# Motors.net
KiCad netlist of a schematic drawn in EAGLE
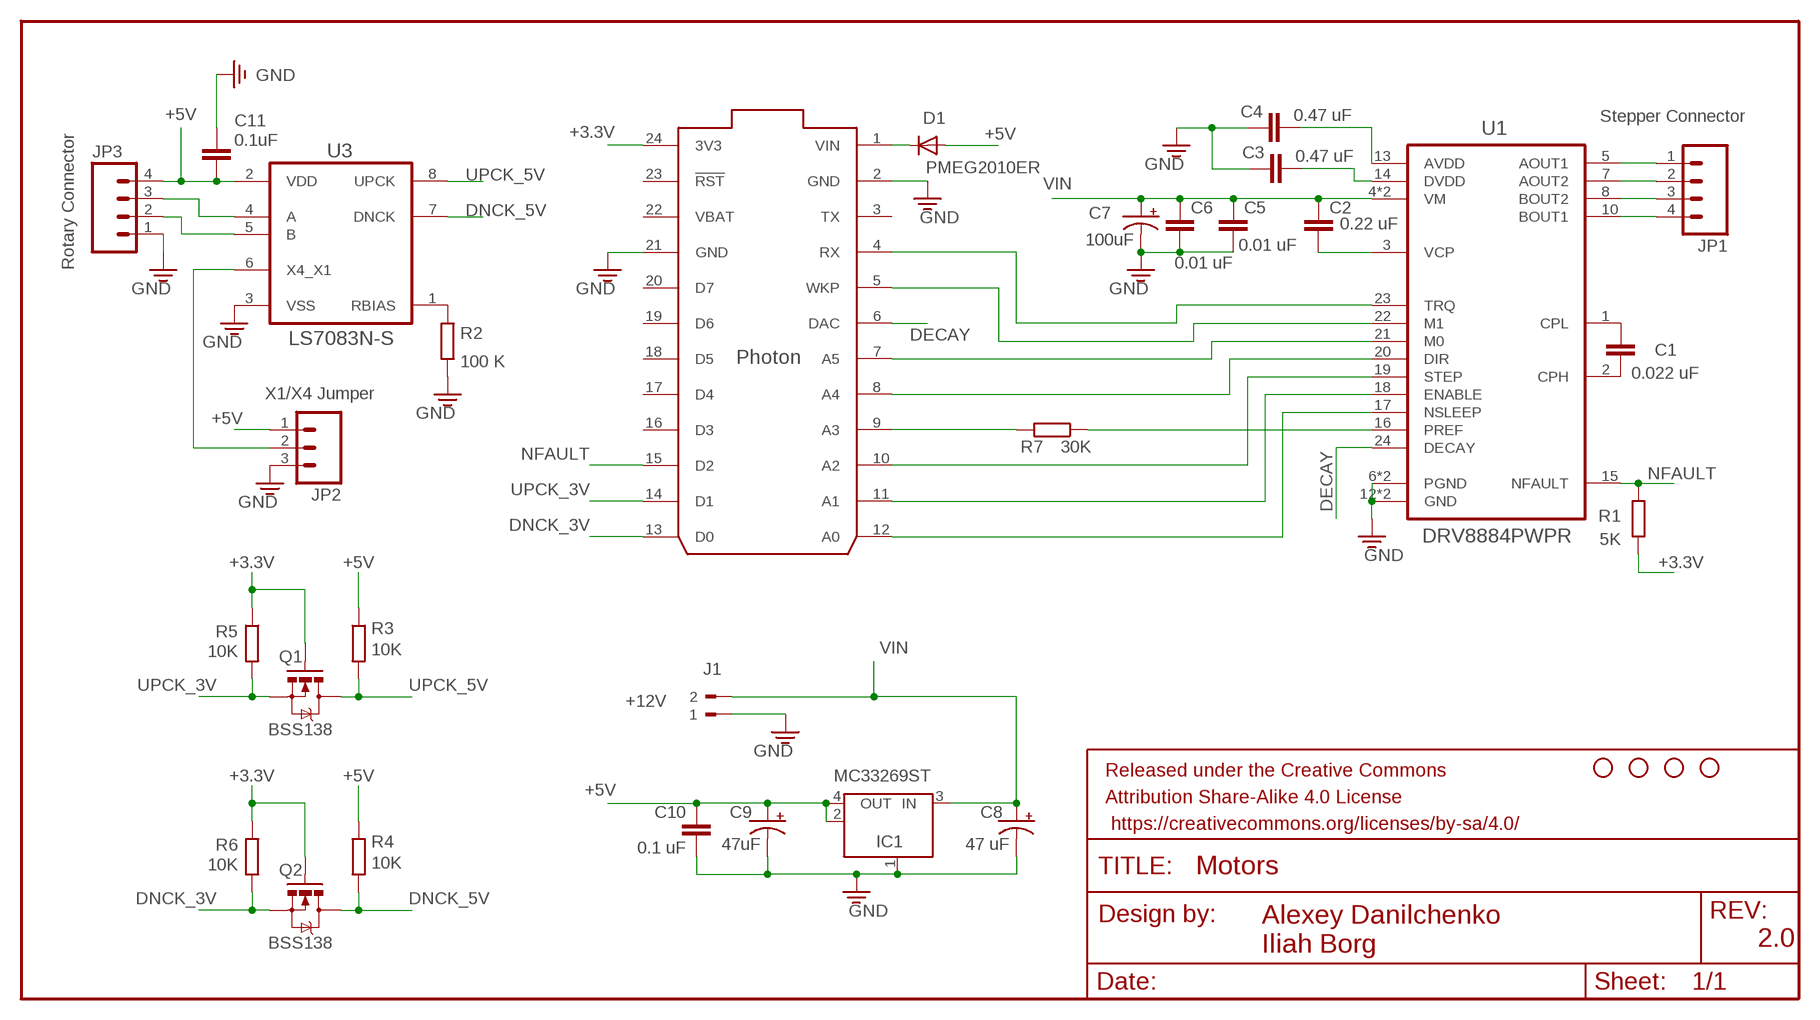
[diagram p0: schematic, sheet 1]

(export (version "E")
  (design (tool "Eeschema 10.0.6"))
  (components
    (comp (ref "C1")
      (value "0.022 uF")
      (footprint "eagle-import:C0805")
      (libsource (lib "eagle-import") (part "C-EUC0805"))
    )
    (comp (ref "C2")
      (value "0.22 uF")
      (footprint "eagle-import:C0805")
      (libsource (lib "eagle-import") (part "C-EUC0805"))
    )
    (comp (ref "C3")
      (value "0.47 uF")
      (footprint "eagle-import:C0805")
      (libsource (lib "eagle-import") (part "C-EUC0805"))
    )
    (comp (ref "C4")
      (value "0.47 uF")
      (footprint "eagle-import:C0805")
      (libsource (lib "eagle-import") (part "C-EUC0805"))
    )
    (comp (ref "C5")
      (value "0.01 uF")
      (footprint "eagle-import:C0805")
      (libsource (lib "eagle-import") (part "C-EUC0805"))
    )
    (comp (ref "C6")
      (value "0.01 uF")
      (footprint "eagle-import:C0805")
      (libsource (lib "eagle-import") (part "C-EUC0805"))
    )
    (comp (ref "C7")
      (value "100uF")
      (footprint "eagle-import:CT7343")
      (libsource (lib "eagle-import") (part "CPOL-USCT7343"))
    )
    (comp (ref "C8")
      (value "47 uF")
      (footprint "eagle-import:CT7343")
      (libsource (lib "eagle-import") (part "CPOL-USCT7343"))
    )
    (comp (ref "C9")
      (value "47uF")
      (footprint "eagle-import:CT7343")
      (libsource (lib "eagle-import") (part "CPOL-USCT7343"))
    )
    (comp (ref "C10")
      (value "0.1 uF")
      (footprint "eagle-import:C0805")
      (libsource (lib "eagle-import") (part "C-EUC0805"))
    )
    (comp (ref "C11")
      (value "0.1uF")
      (footprint "eagle-import:C0805")
      (libsource (lib "eagle-import") (part "C-EUC0805"))
    )
    (comp (ref "D1")
      (value "PMEG2010ER")
      (footprint "eagle-import:SOD123")
      (libsource (lib "eagle-import") (part "DIODE-SOD123"))
    )
    (comp (ref "FRAME1")
      (value "FRAME-LETTER")
      (footprint "eagle-import:CREATIVE_COMMONS")
      (libsource (lib "eagle-import") (part "FRAME-LETTER"))
    )
    (comp (ref "IC1")
      (value "MC33269ST")
      (footprint "eagle-import:SOT223")
      (libsource (lib "eagle-import") (part "MC33269ST"))
    )
    (comp (ref "J1")
      (value "+12V")
      (footprint "eagle-import:WEIDMULLER_PM5.08_2")
      (fields (field (name "MPN") "PM5.08/2/90 BLK"))
      (libsource (lib "eagle-import") (part "PM5.08/2/90BLK"))
    )
    (comp (ref "JP1")
      (value "Stepper Connector")
      (footprint "eagle-import:1X04")
      (libsource (lib "eagle-import") (part "M04PTH"))
    )
    (comp (ref "JP2")
      (value "X1/X4 Jumper")
      (footprint "eagle-import:1X03")
      (libsource (lib "eagle-import") (part "M03PTH"))
    )
    (comp (ref "JP3")
      (value "Rotary Connector")
      (footprint "eagle-import:1X04")
      (libsource (lib "eagle-import") (part "M04PTH"))
    )
    (comp (ref "Q1")
      (value "BSS138")
      (footprint "eagle-import:SOT23-3")
      (libsource (lib "eagle-import") (part "MOSFET-NCHANNELSMD"))
    )
    (comp (ref "Q2")
      (value "BSS138")
      (footprint "eagle-import:SOT23-3")
      (libsource (lib "eagle-import") (part "MOSFET-NCHANNELSMD"))
    )
    (comp (ref "R1")
      (value "5K")
      (footprint "eagle-import:R0805")
      (libsource (lib "eagle-import") (part "R-EU_R0805"))
    )
    (comp (ref "R2")
      (value "100 K")
      (footprint "eagle-import:R0805")
      (libsource (lib "eagle-import") (part "R-EU_R0805"))
    )
    (comp (ref "R3")
      (value "10K")
      (footprint "eagle-import:R0805")
      (libsource (lib "eagle-import") (part "R-EU_R0805"))
    )
    (comp (ref "R4")
      (value "10K")
      (footprint "eagle-import:R0805")
      (libsource (lib "eagle-import") (part "R-EU_R0805"))
    )
    (comp (ref "R5")
      (value "10K")
      (footprint "eagle-import:R0805")
      (libsource (lib "eagle-import") (part "R-EU_R0805"))
    )
    (comp (ref "R6")
      (value "10K")
      (footprint "eagle-import:R0805")
      (libsource (lib "eagle-import") (part "R-EU_R0805"))
    )
    (comp (ref "R7")
      (value "30K")
      (footprint "eagle-import:R0805")
      (libsource (lib "eagle-import") (part "R-EU_R0805"))
    )
    (comp (ref "STANDOFF1")
      (value "STAND-OFF")
      (footprint "eagle-import:STAND-OFF")
      (libsource (lib "eagle-import") (part "STAND-OFF"))
    )
    (comp (ref "STANDOFF2")
      (value "STAND-OFF")
      (footprint "eagle-import:STAND-OFF")
      (libsource (lib "eagle-import") (part "STAND-OFF"))
    )
    (comp (ref "STANDOFF3")
      (value "STAND-OFF")
      (footprint "eagle-import:STAND-OFF")
      (libsource (lib "eagle-import") (part "STAND-OFF"))
    )
    (comp (ref "STANDOFF4")
      (value "STAND-OFF")
      (footprint "eagle-import:STAND-OFF")
      (libsource (lib "eagle-import") (part "STAND-OFF"))
    )
    (comp (ref "U1")
      (value "DRV8884PWPR")
      (footprint "eagle-import:SOP65P640X120-29N")
      (libsource (lib "eagle-import") (part "DRV8884PWPR"))
    )
    (comp (ref "U2")
      (value "PHOTON_WITH_HEADERS")
      (footprint "eagle-import:PHOTON")
      (libsource (lib "eagle-import") (part "PHOTON_WITH_HEADERS"))
    )
    (comp (ref "U3")
      (value "LS7083N-S")
      (footprint "eagle-import:SOIC127P600X175-8N")
      (libsource (lib "eagle-import") (part "LSI7083N-S"))
    )
  )
  (nets
    (net (code "1") (name "/+3.3V") (class "Default")
      (node (ref "Q1") (pin "1") (pinfunction "G_1") (pintype "passive"))
      (node (ref "Q2") (pin "1") (pinfunction "G_1") (pintype "passive"))
      (node (ref "R1") (pin "1") (pinfunction "1_1") (pintype "passive"))
      (node (ref "R5") (pin "1") (pinfunction "1_1") (pintype "passive"))
      (node (ref "R6") (pin "1") (pinfunction "1_1") (pintype "passive"))
      (node (ref "U2") (pin "24") (pinfunction "3V3_24") (pintype "power_in"))
    )
    (net (code "2") (name "/+5V") (class "Default")
      (node (ref "C10") (pin "1") (pinfunction "1_1") (pintype "passive"))
      (node (ref "C11") (pin "2") (pinfunction "2_2") (pintype "passive"))
      (node (ref "C9") (pin "+") (pinfunction "+_+") (pintype "passive"))
      (node (ref "D1") (pin "A") (pinfunction "A_A") (pintype "passive"))
      (node (ref "IC1") (pin "2") (pinfunction "OUT_2") (pintype "passive"))
      (node (ref "IC1") (pin "4") (pinfunction "OUT_4") (pintype "passive"))
      (node (ref "JP2") (pin "1") (pinfunction "1_1") (pintype "passive"))
      (node (ref "JP3") (pin "4") (pinfunction "4_4") (pintype "passive"))
      (node (ref "R3") (pin "1") (pinfunction "1_1") (pintype "passive"))
      (node (ref "R4") (pin "1") (pinfunction "1_1") (pintype "passive"))
      (node (ref "U3") (pin "2") (pinfunction "VDD_2") (pintype "power_in"))
    )
    (net (code "3") (name "/DECAY") (class "Default")
      (node (ref "U1") (pin "24") (pinfunction "DECAY_24") (pintype "input"))
      (node (ref "U2") (pin "6") (pinfunction "DAC_6") (pintype "bidirectional"))
    )
    (net (code "4") (name "/DNCK_3V") (class "Default")
      (node (ref "Q2") (pin "2") (pinfunction "S_2") (pintype "passive"))
      (node (ref "R6") (pin "2") (pinfunction "2_2") (pintype "passive"))
      (node (ref "U2") (pin "13") (pinfunction "D0_13") (pintype "bidirectional"))
    )
    (net (code "5") (name "/DNCK_5V") (class "Default")
      (node (ref "Q2") (pin "3") (pinfunction "D_3") (pintype "passive"))
      (node (ref "R4") (pin "2") (pinfunction "2_2") (pintype "passive"))
      (node (ref "U3") (pin "7") (pinfunction "DNCK_7") (pintype "output"))
    )
    (net (code "6") (name "/NFAULT") (class "Default")
      (node (ref "R1") (pin "2") (pinfunction "2_2") (pintype "passive"))
      (node (ref "U1") (pin "15") (pinfunction "NFAULT_15") (pintype "output"))
      (node (ref "U2") (pin "15") (pinfunction "D2_15") (pintype "bidirectional"))
    )
    (net (code "7") (name "/UPCK_3V") (class "Default")
      (node (ref "Q1") (pin "2") (pinfunction "S_2") (pintype "passive"))
      (node (ref "R5") (pin "2") (pinfunction "2_2") (pintype "passive"))
      (node (ref "U2") (pin "14") (pinfunction "D1_14") (pintype "bidirectional"))
    )
    (net (code "8") (name "/UPCK_5V") (class "Default")
      (node (ref "Q1") (pin "3") (pinfunction "D_3") (pintype "passive"))
      (node (ref "R3") (pin "2") (pinfunction "2_2") (pintype "passive"))
      (node (ref "U3") (pin "8") (pinfunction "UPCK_8") (pintype "output"))
    )
    (net (code "9") (name "/VBAT") (class "Default")
      (node (ref "U2") (pin "22") (pinfunction "VBAT_22") (pintype "power_in"))
    )
    (net (code "10") (name "/VIN") (class "Default")
      (node (ref "C2") (pin "1") (pinfunction "1_1") (pintype "passive"))
      (node (ref "C5") (pin "1") (pinfunction "1_1") (pintype "passive"))
      (node (ref "C6") (pin "1") (pinfunction "1_1") (pintype "passive"))
      (node (ref "C7") (pin "+") (pinfunction "+_+") (pintype "passive"))
      (node (ref "C8") (pin "+") (pinfunction "+_+") (pintype "passive"))
      (node (ref "IC1") (pin "3") (pinfunction "IN_3") (pintype "input"))
      (node (ref "J1") (pin "2") (pinfunction "2_2") (pintype "passive"))
      (node (ref "U1") (pin "11") (pinfunction "VM_11") (pintype "power_in"))
      (node (ref "U1") (pin "4") (pinfunction "VM_4") (pintype "power_in"))
    )
    (net (code "11") (name "GND") (class "Default")
      (node (ref "C10") (pin "2") (pinfunction "2_2") (pintype "passive"))
      (node (ref "C11") (pin "1") (pinfunction "1_1") (pintype "passive"))
      (node (ref "C3") (pin "2") (pinfunction "2_2") (pintype "passive"))
      (node (ref "C4") (pin "2") (pinfunction "2_2") (pintype "passive"))
      (node (ref "C5") (pin "2") (pinfunction "2_2") (pintype "passive"))
      (node (ref "C6") (pin "2") (pinfunction "2_2") (pintype "passive"))
      (node (ref "C7") (pin "-") (pinfunction "-_-") (pintype "passive"))
      (node (ref "C8") (pin "-") (pinfunction "-_-") (pintype "passive"))
      (node (ref "C9") (pin "-") (pinfunction "-_-") (pintype "passive"))
      (node (ref "IC1") (pin "1") (pinfunction "GND/ADJ_1") (pintype "input"))
      (node (ref "J1") (pin "1") (pinfunction "1_1") (pintype "passive"))
      (node (ref "JP2") (pin "3") (pinfunction "3_3") (pintype "passive"))
      (node (ref "JP3") (pin "1") (pinfunction "1_1") (pintype "passive"))
      (node (ref "R2") (pin "2") (pinfunction "2_2") (pintype "passive"))
      (node (ref "U1") (pin "12") (pinfunction "GND_12") (pintype "passive"))
      (node (ref "U1") (pin "25") (pinfunction "GND_25") (pintype "passive"))
      (node (ref "U1") (pin "6") (pinfunction "PGND_6") (pintype "passive"))
      (node (ref "U1") (pin "9") (pinfunction "PGND_9") (pintype "passive"))
      (node (ref "U2") (pin "2") (pinfunction "GND_2") (pintype "power_in"))
      (node (ref "U2") (pin "21") (pinfunction "GND_21") (pintype "power_in"))
      (node (ref "U3") (pin "3") (pinfunction "VSS_3") (pintype "power_in"))
    )
    (net (code "12") (name "Net-(U1-AOUT1)") (class "Default")
      (node (ref "JP1") (pin "1") (pinfunction "1_1") (pintype "passive"))
      (node (ref "U1") (pin "5") (pinfunction "AOUT1_5") (pintype "output"))
    )
    (net (code "13") (name "Net-(U1-AOUT2)") (class "Default")
      (node (ref "JP1") (pin "2") (pinfunction "2_2") (pintype "passive"))
      (node (ref "U1") (pin "7") (pinfunction "AOUT2_7") (pintype "output"))
    )
    (net (code "14") (name "Net-(U1-AVDD)") (class "Default")
      (node (ref "C4") (pin "1") (pinfunction "1_1") (pintype "passive"))
      (node (ref "U1") (pin "13") (pinfunction "AVDD_13") (pintype "power_in"))
    )
    (net (code "15") (name "Net-(U1-BOUT1)") (class "Default")
      (node (ref "JP1") (pin "4") (pinfunction "4_4") (pintype "passive"))
      (node (ref "U1") (pin "10") (pinfunction "BOUT1_10") (pintype "output"))
    )
    (net (code "16") (name "Net-(U1-BOUT2)") (class "Default")
      (node (ref "JP1") (pin "3") (pinfunction "3_3") (pintype "passive"))
      (node (ref "U1") (pin "8") (pinfunction "BOUT2_8") (pintype "output"))
    )
    (net (code "17") (name "Net-(U1-CPH)") (class "Default")
      (node (ref "C1") (pin "1") (pinfunction "1_1") (pintype "passive"))
      (node (ref "U1") (pin "2") (pinfunction "CPH_2") (pintype "input"))
    )
    (net (code "18") (name "Net-(U1-CPL)") (class "Default")
      (node (ref "C1") (pin "2") (pinfunction "2_2") (pintype "passive"))
      (node (ref "U1") (pin "1") (pinfunction "CPL_1") (pintype "input"))
    )
    (net (code "19") (name "Net-(U1-DIR)") (class "Default")
      (node (ref "U1") (pin "20") (pinfunction "DIR_20") (pintype "input"))
      (node (ref "U2") (pin "8") (pinfunction "A4_8") (pintype "bidirectional"))
    )
    (net (code "20") (name "Net-(U1-DVDD)") (class "Default")
      (node (ref "C3") (pin "1") (pinfunction "1_1") (pintype "passive"))
      (node (ref "U1") (pin "14") (pinfunction "DVDD_14") (pintype "power_in"))
    )
    (net (code "21") (name "Net-(U1-ENABLE)") (class "Default")
      (node (ref "U1") (pin "18") (pinfunction "ENABLE_18") (pintype "input"))
      (node (ref "U2") (pin "11") (pinfunction "A1_11") (pintype "bidirectional"))
    )
    (net (code "22") (name "Net-(U1-M0)") (class "Default")
      (node (ref "U1") (pin "21") (pinfunction "M0_21") (pintype "input"))
      (node (ref "U2") (pin "7") (pinfunction "A5_7") (pintype "bidirectional"))
    )
    (net (code "23") (name "Net-(U1-M1)") (class "Default")
      (node (ref "U1") (pin "22") (pinfunction "M1_22") (pintype "input"))
      (node (ref "U2") (pin "5") (pinfunction "WKP_5") (pintype "bidirectional"))
    )
    (net (code "24") (name "Net-(U1-NSLEEP)") (class "Default")
      (node (ref "U1") (pin "17") (pinfunction "NSLEEP_17") (pintype "input"))
      (node (ref "U2") (pin "12") (pinfunction "A0_12") (pintype "bidirectional"))
    )
    (net (code "25") (name "Net-(U1-PREF)") (class "Default")
      (node (ref "R7") (pin "1") (pinfunction "1_1") (pintype "passive"))
      (node (ref "U1") (pin "16") (pinfunction "PREF_16") (pintype "input"))
    )
    (net (code "26") (name "Net-(U1-STEP)") (class "Default")
      (node (ref "U1") (pin "19") (pinfunction "STEP_19") (pintype "input"))
      (node (ref "U2") (pin "10") (pinfunction "A2_10") (pintype "bidirectional"))
    )
    (net (code "27") (name "Net-(U1-TRQ)") (class "Default")
      (node (ref "U1") (pin "23") (pinfunction "TRQ_23") (pintype "input"))
      (node (ref "U2") (pin "4") (pinfunction "RX_4") (pintype "bidirectional"))
    )
    (net (code "28") (name "Net-(U1-VCP)") (class "Default")
      (node (ref "C2") (pin "2") (pinfunction "2_2") (pintype "passive"))
      (node (ref "U1") (pin "3") (pinfunction "VCP_3") (pintype "input"))
    )
    (net (code "29") (name "Net-(U2-A3)") (class "Default")
      (node (ref "R7") (pin "2") (pinfunction "2_2") (pintype "passive"))
      (node (ref "U2") (pin "9") (pinfunction "A3_9") (pintype "bidirectional"))
    )
    (net (code "30") (name "Net-(U2-VIN)") (class "Default")
      (node (ref "D1") (pin "C") (pinfunction "C_C") (pintype "passive"))
      (node (ref "U2") (pin "1") (pinfunction "VIN_1") (pintype "power_in"))
    )
    (net (code "31") (name "Net-(U3-A)") (class "Default")
      (node (ref "JP3") (pin "3") (pinfunction "3_3") (pintype "passive"))
      (node (ref "U3") (pin "4") (pinfunction "A_4") (pintype "input"))
    )
    (net (code "32") (name "Net-(U3-B)") (class "Default")
      (node (ref "JP3") (pin "2") (pinfunction "2_2") (pintype "passive"))
      (node (ref "U3") (pin "5") (pinfunction "B_5") (pintype "input"))
    )
    (net (code "33") (name "Net-(U3-RBIAS)") (class "Default")
      (node (ref "R2") (pin "1") (pinfunction "1_1") (pintype "passive"))
      (node (ref "U3") (pin "1") (pinfunction "RBIAS_1") (pintype "input"))
    )
    (net (code "34") (name "Net-(U3-X4_X1)") (class "Default")
      (node (ref "JP2") (pin "2") (pinfunction "2_2") (pintype "passive"))
      (node (ref "U3") (pin "6") (pinfunction "X4_X1_6") (pintype "input"))
    )
    (net (code "35") (name "unconnected-(U2-D3-Pad16)") (class "Default")
      (node (ref "U2") (pin "16") (pinfunction "D3_16") (pintype "bidirectional"))
    )
    (net (code "36") (name "unconnected-(U2-D4-Pad17)") (class "Default")
      (node (ref "U2") (pin "17") (pinfunction "D4_17") (pintype "bidirectional"))
    )
    (net (code "37") (name "unconnected-(U2-D5-Pad18)") (class "Default")
      (node (ref "U2") (pin "18") (pinfunction "D5_18") (pintype "bidirectional"))
    )
    (net (code "38") (name "unconnected-(U2-D6-Pad19)") (class "Default")
      (node (ref "U2") (pin "19") (pinfunction "D6_19") (pintype "bidirectional"))
    )
    (net (code "39") (name "unconnected-(U2-D7-Pad20)") (class "Default")
      (node (ref "U2") (pin "20") (pinfunction "D7_20") (pintype "bidirectional"))
    )
    (net (code "40") (name "unconnected-(U2-TX-Pad3)") (class "Default")
      (node (ref "U2") (pin "3") (pinfunction "TX_3") (pintype "bidirectional"))
    )
    (net (code "41") (name "unconnected-(U2-~{RST}-Pad23)") (class "Default")
      (node (ref "U2") (pin "23") (pinfunction "~{RST}_23") (pintype "bidirectional"))
    )
  )
)
